# SUP_1_2_1_8.net
KiCad netlist of a schematic drawn in Altium Designer
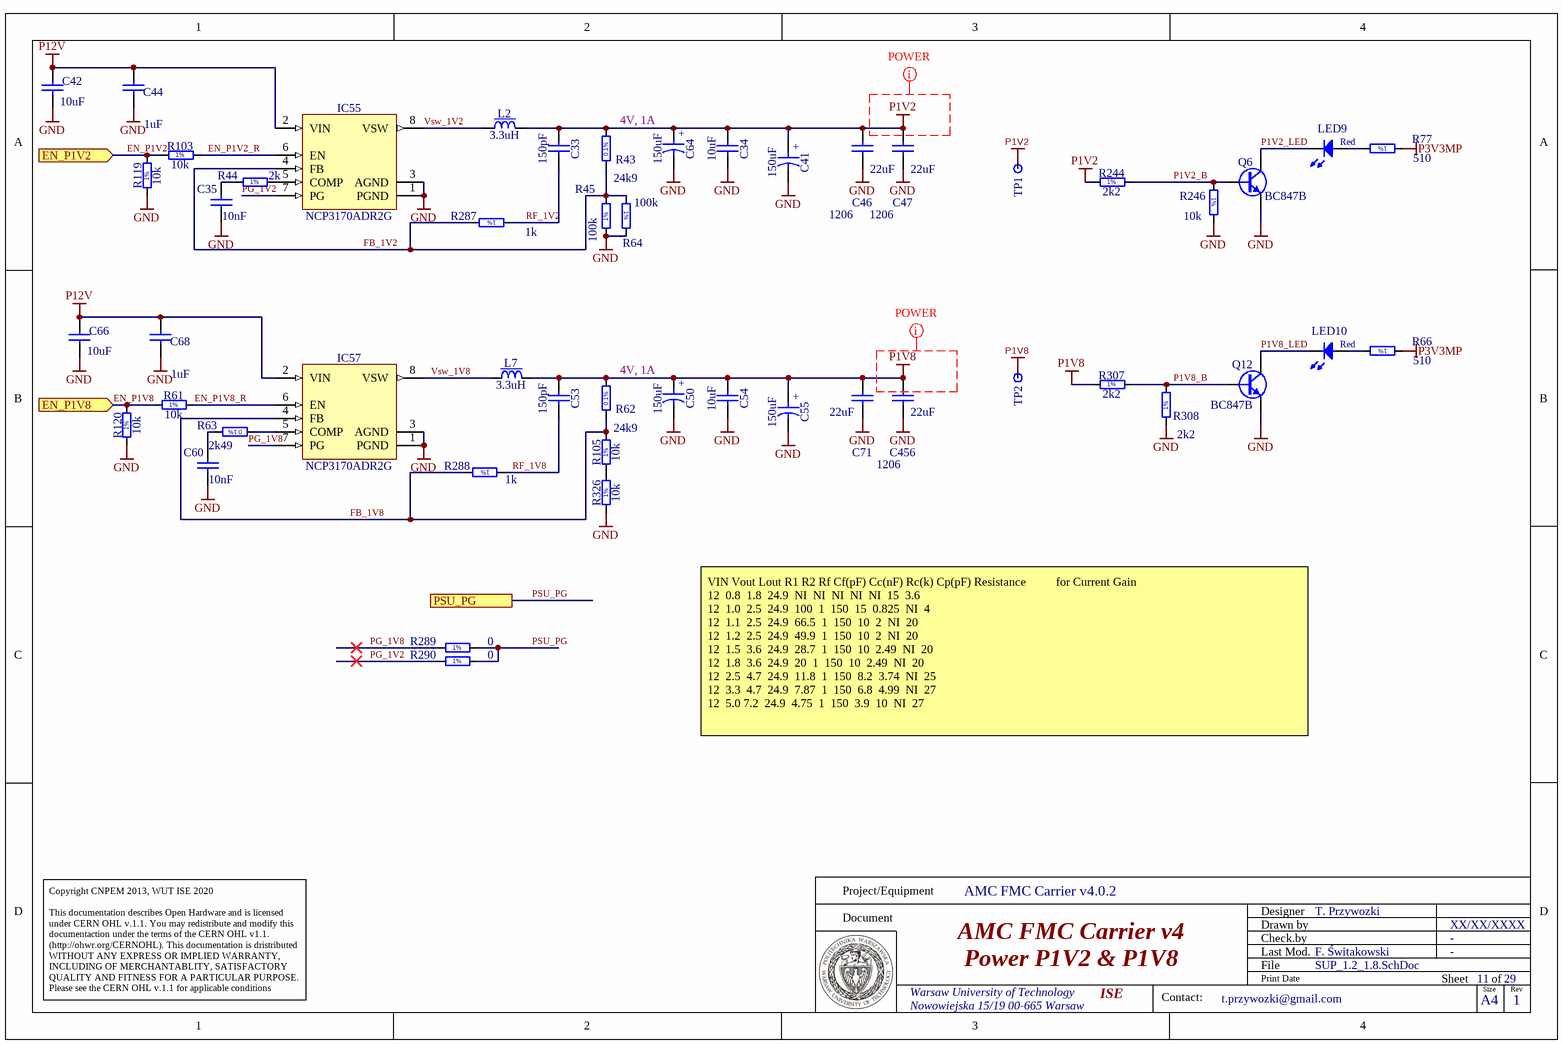
[diagram p0: SUP_1.2_1.8.SchDoc]

(export (version "E")
  (design (tool "Eeschema 10.0.6"))
  (components
    (comp (ref "C33")
      (value "150pF")
      (footprint "CAPC1608X87N")
      (description "Non-polarised capacitor")
      (fields
        (field (name "PART NUMBER") "CC0603_150PF_50V_5%_NP0")
        (field (name "VOLTAGE") "50V")
        (field (name "AUTHOR") "CERN DEM JLC")
      )
      (libsource (lib "Capacitors") (part "Capacitor - non polarized"))
    )
    (comp (ref "C34")
      (value "10uF")
      (footprint "CAPC2012X135N")
      (description "Non-polarised capacitor")
      (fields
        (field (name "PART NUMBER") "CC0805_10UF_16V_10%_X5R")
        (field (name "VOLTAGE") "16V")
        (field (name "AUTHOR") "CERN DEM JLC")
      )
      (libsource (lib "Capacitors") (part "Capacitor - non polarized"))
    )
    (comp (ref "C35")
      (value "10nF")
      (footprint "CAPC1005X55N")
      (description "Non-polarised capacitor")
      (fields
        (field (name "PART NUMBER") "CC0402_10NF_16V_10%_X7R")
        (field (name "VOLTAGE") "16V")
        (field (name "AUTHOR") "CERN DEM JLC")
      )
      (libsource (lib "Capacitors") (part "Capacitor - non polarized"))
    )
    (comp (ref "C41")
      (value "150uF")
      (footprint "CAPMP7343X200N")
      (description "Polarised capacitor")
      (fields
        (field (name "PART NUMBER") "CAEM7343-20_150UF_4V_20%_LESR0016")
        (field (name "VOLTAGE") "4V")
        (field (name "AUTHOR") "CERN DEM JLC")
      )
      (libsource (lib "Capacitors") (part "Capacitor - polarized"))
    )
    (comp (ref "C42")
      (value "10uF")
      (footprint "CAPC2012X135N")
      (description "Non-polarised capacitor")
      (fields
        (field (name "PART NUMBER") "CC0805_10UF_16V_10%_X5R")
        (field (name "VOLTAGE") "16V")
        (field (name "AUTHOR") "CERN DEM JLC")
      )
      (libsource (lib "Capacitors") (part "Capacitor - non polarized"))
    )
    (comp (ref "C44")
      (value "1uF")
      (footprint "CAPC1608X87N")
      (description "Non-polarised capacitor")
      (fields
        (field (name "PART NUMBER") "CC0603_1UF_16V_10%_X7R")
        (field (name "VOLTAGE") "16V")
        (field (name "AUTHOR") "CERN DEM JLC")
      )
      (libsource (lib "Capacitors") (part "Capacitor - non polarized"))
    )
    (comp (ref "C46")
      (value "22uF")
      (footprint "CAPC3216X180N")
      (description "Non-polarised capacitor")
      (fields
        (field (name "PART NUMBER") "CC1206_22UF_10V_10%_X7R")
        (field (name "VOLTAGE") "10V")
        (field (name "CASE") "1206")
        (field (name "AUTHOR") "CERN DEM JLC")
      )
      (libsource (lib "Capacitors") (part "Capacitor - non polarized"))
    )
    (comp (ref "C47")
      (value "22uF")
      (footprint "CAPC3216X180N")
      (description "Non-polarised capacitor")
      (fields
        (field (name "PART NUMBER") "CC1206_22UF_10V_10%_X7R")
        (field (name "VOLTAGE") "10V")
        (field (name "CASE") "1206")
        (field (name "AUTHOR") "CERN DEM JLC")
      )
      (libsource (lib "Capacitors") (part "Capacitor - non polarized"))
    )
    (comp (ref "C50")
      (value "150uF")
      (footprint "CAPMP7343X200N")
      (description "Polarised capacitor")
      (fields
        (field (name "PART NUMBER") "CAEM7343-20_150UF_4V_20%_LESR0016")
        (field (name "VOLTAGE") "4V")
        (field (name "AUTHOR") "CERN DEM JLC")
      )
      (libsource (lib "Capacitors") (part "Capacitor - polarized"))
    )
    (comp (ref "C53")
      (value "150pF")
      (footprint "CAPC1608X87N")
      (description "Non-polarised capacitor")
      (fields
        (field (name "PART NUMBER") "CC0603_150PF_50V_5%_NP0")
        (field (name "VOLTAGE") "50V")
        (field (name "AUTHOR") "CERN DEM JLC")
      )
      (libsource (lib "Capacitors") (part "Capacitor - non polarized"))
    )
    (comp (ref "C54")
      (value "10uF")
      (footprint "CAPC2012X135N")
      (description "Non-polarised capacitor")
      (fields
        (field (name "PART NUMBER") "CC0805_10UF_16V_10%_X5R")
        (field (name "VOLTAGE") "16V")
        (field (name "AUTHOR") "CERN DEM JLC")
      )
      (libsource (lib "Capacitors") (part "Capacitor - non polarized"))
    )
    (comp (ref "C55")
      (value "150uF")
      (footprint "CAPMP7343X200N")
      (description "Polarised capacitor")
      (fields
        (field (name "PART NUMBER") "CAEM7343-20_150UF_4V_20%_LESR0016")
        (field (name "VOLTAGE") "4V")
        (field (name "AUTHOR") "CERN DEM JLC")
      )
      (libsource (lib "Capacitors") (part "Capacitor - polarized"))
    )
    (comp (ref "C60")
      (value "10nF")
      (footprint "CAPC1005X55N")
      (description "Non-polarised capacitor")
      (fields
        (field (name "PART NUMBER") "CC0402_10NF_16V_10%_X7R")
        (field (name "VOLTAGE") "16V")
        (field (name "AUTHOR") "CERN DEM JLC")
      )
      (libsource (lib "Capacitors") (part "Capacitor - non polarized"))
    )
    (comp (ref "C64")
      (value "150uF")
      (footprint "CAPMP7343X200N")
      (description "Polarised capacitor")
      (fields
        (field (name "PART NUMBER") "CAEM7343-20_150UF_4V_20%_LESR0016")
        (field (name "VOLTAGE") "4V")
        (field (name "AUTHOR") "CERN DEM JLC")
      )
      (libsource (lib "Capacitors") (part "Capacitor - polarized"))
    )
    (comp (ref "C66")
      (value "10uF")
      (footprint "CAPC2012X135N")
      (description "Non-polarised capacitor")
      (fields
        (field (name "PART NUMBER") "CC0805_10UF_16V_10%_X5R")
        (field (name "VOLTAGE") "16V")
        (field (name "AUTHOR") "CERN DEM JLC")
      )
      (libsource (lib "Capacitors") (part "Capacitor - non polarized"))
    )
    (comp (ref "C68")
      (value "1uF")
      (footprint "CAPC1608X87N")
      (description "Non-polarised capacitor")
      (fields
        (field (name "PART NUMBER") "CC0603_1UF_16V_10%_X7R")
        (field (name "VOLTAGE") "16V")
        (field (name "AUTHOR") "CERN DEM JLC")
      )
      (libsource (lib "Capacitors") (part "Capacitor - non polarized"))
    )
    (comp (ref "C71")
      (value "22uF")
      (footprint "CAPC3216X180N")
      (description "Non-polarised capacitor")
      (fields
        (field (name "PART NUMBER") "CC1206_22UF_10V_10%_X7R")
        (field (name "VOLTAGE") "10V")
        (field (name "AUTHOR") "CERN DEM JLC")
      )
      (libsource (lib "Capacitors") (part "Capacitor - non polarized"))
    )
    (comp (ref "C456")
      (value "22uF")
      (footprint "CAPC3216X180N")
      (description "Non-polarised capacitor")
      (fields
        (field (name "PART NUMBER") "CC1206_22UF_10V_10%_X7R")
        (field (name "VOLTAGE") "10V")
        (field (name "CASE") "1206")
        (field (name "AUTHOR") "CERN DEM JLC")
      )
      (libsource (lib "Capacitors") (part "Capacitor - non polarized"))
    )
    (comp (ref "IC55")
      (value "NCP3170ADR2G")
      (footprint "SOIC127P600X175-8N")
      (description "Synchronous PWM Switching Converter")
      (fields (field (name "MANUFACTURER") "ON SEMICONDUCTOR") (field (name "AUTHOR") "CERN DEM MR"))
      (libsource (lib "ICs And Semiconductors") (part "NCP3170ADR2G"))
    )
    (comp (ref "IC57")
      (value "NCP3170ADR2G")
      (footprint "SOIC127P600X175-8N")
      (description "Synchronous PWM Switching Converter")
      (fields (field (name "MANUFACTURER") "ON SEMICONDUCTOR") (field (name "AUTHOR") "CERN DEM MR"))
      (libsource (lib "ICs And Semiconductors") (part "NCP3170ADR2G"))
    )
    (comp (ref "L2")
      (value "3.3uH")
      (footprint "IND_WURTH_WE-PD4_L")
      (description "Inductor With Core")
      (fields
        (field (name "PART NUMBER") "IND_3.3UH_20%_WURTH_WE-PD4_74456033")
        (field (name "POWER") "5.3A")
        (field (name "AUTHOR") "CERN DEM JLC")
      )
      (libsource (lib "Inductors & Transformers") (part "Inductor With Magnetic core"))
    )
    (comp (ref "L7")
      (value "3.3uH")
      (footprint "IND_WURTH_WE-PD4_L")
      (description "Inductor With Core")
      (fields
        (field (name "PART NUMBER") "IND_3.3UH_20%_WURTH_WE-PD4_74456033")
        (field (name "POWER") "5.3A")
        (field (name "AUTHOR") "CERN DEM JLC")
      )
      (libsource (lib "Inductors & Transformers") (part "Inductor With Magnetic core"))
    )
    (comp (ref "LED9")
      (value "Red")
      (footprint "LED_KINGBRIGHT_KPH-1608SURCK")
      (description "LED Red 1C 2A")
      (fields
        (field (name "PART NUMBER") "LED_KINGBRIGHT_KPH-1608SURCK")
        (field (name "MANUFACTURER") "KINGBRIGHT")
        (field (name "AUTHOR") "CERN DEM JLC")
      )
      (libsource (lib "ICs And Semiconductors") (part "LED Red 1C 2A"))
    )
    (comp (ref "LED10")
      (value "Red")
      (footprint "LED_KINGBRIGHT_KPH-1608SURCK")
      (description "LED Red 1C 2A")
      (fields
        (field (name "PART NUMBER") "LED_KINGBRIGHT_KPH-1608SURCK")
        (field (name "MANUFACTURER") "KINGBRIGHT")
        (field (name "AUTHOR") "CERN DEM JLC")
      )
      (libsource (lib "ICs And Semiconductors") (part "LED Red 1C 2A"))
    )
    (comp (ref "Q6")
      (value "BC847B")
      (footprint "SOT95P230X110-3N")
      (description "NPN Transistor")
      (fields (field (name "MANUFACTURER") "NXP SEMICONDUCTORS") (field (name "AUTHOR") "CERN DEM JLC"))
      (libsource (lib "ICs And Semiconductors") (part "NPN B1 E2 C3"))
    )
    (comp (ref "Q12")
      (value "BC847B")
      (footprint "SOT95P230X110-3N")
      (description "NPN Transistor")
      (fields (field (name "MANUFACTURER") "NXP SEMICONDUCTORS") (field (name "AUTHOR") "CERN DEM JLC"))
      (libsource (lib "ICs And Semiconductors") (part "NPN B1 E2 C3"))
    )
    (comp (ref "R43")
      (value "24k9")
      (footprint "RESC1608X55N")
      (description "Resistor - 0.1%")
      (fields
        (field (name "PART NUMBER") "R0603_24K9_0.1%_0.063W_10PPM")
        (field (name "POWER") "0.063W")
        (field (name "AUTHOR") "CERN DEM JLC")
      )
      (libsource (lib "Resistors") (part "Resistor - 0.1%"))
    )
    (comp (ref "R44")
      (value "2k")
      (footprint "RESC1608X55N")
      (description "Resistor - 1%")
      (fields
        (field (name "PART NUMBER") "R0603_2K_1%_0.1W_100PPM")
        (field (name "POWER") "0.1W")
        (field (name "AUTHOR") "CERN DEM JLC")
      )
      (libsource (lib "Resistors") (part "Resistor - 1%"))
    )
    (comp (ref "R45")
      (value "100k")
      (footprint "RESC1005X40N")
      (description "Resistor - 1%")
      (fields
        (field (name "PART NUMBER") "R0402_100K_1%_0.0625W_100PPM")
        (field (name "POWER") "0.0625W")
        (field (name "AUTHOR") "CERN DEM JLC")
      )
      (libsource (lib "Resistors") (part "Resistor - 1%"))
    )
    (comp (ref "R61")
      (value "10k")
      (footprint "RESC1005X40N")
      (description "Resistor - 1%")
      (fields
        (field (name "PART NUMBER") "R0402_10K_1%_0.0625W_100PPM")
        (field (name "POWER") "0.0625W")
        (field (name "AUTHOR") "CERN DEM JLC")
      )
      (libsource (lib "Resistors") (part "Resistor - 1%"))
    )
    (comp (ref "R62")
      (value "24k9")
      (footprint "RESC1608X55N")
      (description "Resistor - 0.1%")
      (fields
        (field (name "PART NUMBER") "R0603_24K9_0.1%_0.063W_10PPM")
        (field (name "POWER") "0.063W")
        (field (name "AUTHOR") "CERN DEM JLC")
      )
      (libsource (lib "Resistors") (part "Resistor - 0.1%"))
    )
    (comp (ref "R63")
      (value "2k49")
      (footprint "RESC1608X55N")
      (description "Resistor - 0.1%")
      (fields
        (field (name "PART NUMBER") "R0603_2K49_0.1%_0.063W_10PPM")
        (field (name "POWER") "0.063W")
        (field (name "AUTHOR") "CERN DEM JLC")
      )
      (libsource (lib "Resistors") (part "Resistor - 0.1%"))
    )
    (comp (ref "R64")
      (value "100k")
      (footprint "RESC1005X40N")
      (description "Resistor - 1%")
      (fields
        (field (name "PART NUMBER") "R0402_100K_1%_0.0625W_100PPM")
        (field (name "POWER") "0.0625W")
        (field (name "AUTHOR") "CERN DEM JLC")
      )
      (libsource (lib "Resistors") (part "Resistor - 1%"))
    )
    (comp (ref "R66")
      (value "510")
      (footprint "RESC1005X40N")
      (description "Resistor - 1%")
      (fields
        (field (name "PART NUMBER") "R0402_510R_1%_0.0625W_100PPM")
        (field (name "POWER") "0.0625W")
        (field (name "AUTHOR") "CERN DEM JLC")
      )
      (libsource (lib "Resistors") (part "Resistor - 1%"))
    )
    (comp (ref "R77")
      (value "510")
      (footprint "RESC1005X40N")
      (description "Resistor - 1%")
      (fields
        (field (name "PART NUMBER") "R0402_510R_1%_0.0625W_100PPM")
        (field (name "POWER") "0.0625W")
        (field (name "AUTHOR") "CERN DEM JLC")
      )
      (libsource (lib "Resistors") (part "Resistor - 1%"))
    )
    (comp (ref "R103")
      (value "10k")
      (footprint "RESC1005X40N")
      (description "Resistor - 1%")
      (fields
        (field (name "PART NUMBER") "R0402_10K_1%_0.0625W_100PPM")
        (field (name "POWER") "0.0625W")
        (field (name "AUTHOR") "CERN DEM JLC")
      )
      (libsource (lib "Resistors") (part "Resistor - 1%"))
    )
    (comp (ref "R105")
      (value "10k")
      (footprint "RESC1005X40N")
      (description "Resistor - 1%")
      (fields
        (field (name "PART NUMBER") "R0402_10K_1%_0.0625W_100PPM")
        (field (name "POWER") "0.0625W")
        (field (name "AUTHOR") "CERN DEM JLC")
      )
      (libsource (lib "Resistors") (part "Resistor - 1%"))
    )
    (comp (ref "R119")
      (value "10k")
      (footprint "RESC1005X40N")
      (description "Resistor - 1%")
      (fields
        (field (name "PART NUMBER") "R0402_10K_1%_0.0625W_100PPM")
        (field (name "POWER") "0.0625W")
        (field (name "AUTHOR") "CERN DEM JLC")
      )
      (libsource (lib "Resistors") (part "Resistor - 1%"))
    )
    (comp (ref "R120")
      (value "10k")
      (footprint "RESC1005X40N")
      (description "Resistor - 1%")
      (fields
        (field (name "PART NUMBER") "R0402_10K_1%_0.0625W_100PPM")
        (field (name "POWER") "0.0625W")
        (field (name "AUTHOR") "CERN DEM JLC")
      )
      (libsource (lib "Resistors") (part "Resistor - 1%"))
    )
    (comp (ref "R244")
      (value "2k2")
      (footprint "RESC1005X40N")
      (description "Resistor - 1%")
      (fields
        (field (name "PART NUMBER") "R0402_2K2_1%_0.0625W_100PPM")
        (field (name "POWER") "0.0625W")
        (field (name "AUTHOR") "CERN DEM JLC")
      )
      (libsource (lib "Resistors") (part "Resistor - 1%"))
    )
    (comp (ref "R246")
      (value "10k")
      (footprint "RESC1005X40N")
      (description "Resistor - 1%")
      (fields
        (field (name "PART NUMBER") "R0402_10K_1%_0.0625W_100PPM")
        (field (name "POWER") "0.0625W")
        (field (name "AUTHOR") "CERN DEM JLC")
      )
      (libsource (lib "Resistors") (part "Resistor - 1%"))
    )
    (comp (ref "R287")
      (value "1k")
      (footprint "RESC1005X40N")
      (description "Resistor - 1%")
      (fields
        (field (name "PART NUMBER") "R0402_1K_1%_0.0625W_100PPM")
        (field (name "POWER") "0.0625W")
        (field (name "AUTHOR") "CERN DEM JLC")
      )
      (libsource (lib "Resistors") (part "Resistor - 1%"))
    )
    (comp (ref "R288")
      (value "1k")
      (footprint "RESC1005X40N")
      (description "Resistor - 1%")
      (fields
        (field (name "PART NUMBER") "R0402_1K_1%_0.0625W_100PPM")
        (field (name "POWER") "0.0625W")
        (field (name "AUTHOR") "CERN DEM JLC")
      )
      (libsource (lib "Resistors") (part "Resistor - 1%"))
    )
    (comp (ref "R289")
      (value "0")
      (footprint "RESC1005X40N")
      (description "Resistor - 1%")
      (fields
        (field (name "PART NUMBER") "R0402_0R_JUMPER")
        (field (name "MANUFACTURER") "GENERIC")
        (field (name "AUTHOR") "CERN DEM JLC")
      )
      (libsource (lib "Resistors") (part "Resistor - 1%"))
    )
    (comp (ref "R290")
      (value "0")
      (footprint "RESC1005X40N")
      (description "Resistor - 1%")
      (fields
        (field (name "PART NUMBER") "R0402_0R_JUMPER")
        (field (name "MANUFACTURER") "GENERIC")
        (field (name "AUTHOR") "CERN DEM JLC")
      )
      (libsource (lib "Resistors") (part "Resistor - 1%"))
    )
    (comp (ref "R307")
      (value "2k2")
      (footprint "RESC1005X40N")
      (description "Resistor - 1%")
      (fields
        (field (name "PART NUMBER") "R0402_2K2_1%_0.0625W_100PPM")
        (field (name "POWER") "0.0625W")
        (field (name "AUTHOR") "CERN DEM JLC")
      )
      (libsource (lib "Resistors") (part "Resistor - 1%"))
    )
    (comp (ref "R308")
      (value "2k2")
      (footprint "RESC1005X40N")
      (description "Resistor - 1%")
      (fields
        (field (name "PART NUMBER") "R0402_2K2_1%_0.0625W_100PPM")
        (field (name "POWER") "0.0625W")
        (field (name "AUTHOR") "CERN DEM JLC")
      )
      (libsource (lib "Resistors") (part "Resistor - 1%"))
    )
    (comp (ref "R326")
      (value "10k")
      (footprint "RESC1005X40N")
      (description "Resistor - 1%")
      (fields
        (field (name "PART NUMBER") "R0402_10K_1%_0.0625W_100PPM")
        (field (name "POWER") "0.0625W")
        (field (name "AUTHOR") "CERN DEM JLC")
      )
      (libsource (lib "Resistors") (part "Resistor - 1%"))
    )
    (comp (ref "TP1")
      (value "Test Point")
      (footprint "TPS127")
      (fields (field (name "PART NUMBER") "SMD_PAD_1.27X1.27MM") (field (name "AUTHOR") "CERN DEM JLC"))
      (libsource (lib "Eletro-mechanical") (part "Test Point"))
    )
    (comp (ref "TP2")
      (value "Test Point")
      (footprint "TPS127")
      (fields (field (name "PART NUMBER") "SMD_PAD_1.27X1.27MM") (field (name "AUTHOR") "CERN DEM JLC"))
      (libsource (lib "Eletro-mechanical") (part "Test Point"))
    )
  )
  (nets
    (net (code "1") (name "/EN_P1V2") (class "Default")
      (node (ref "R103") (pin "1") (pinfunction "1_1") (pintype "passive"))
      (node (ref "R119") (pin "2") (pinfunction "2_2") (pintype "passive"))
    )
    (net (code "2") (name "/EN_P1V2_R") (class "Default")
      (node (ref "IC55") (pin "6") (pinfunction "EN_6") (pintype "input"))
      (node (ref "R103") (pin "2") (pinfunction "2_2") (pintype "passive"))
    )
    (net (code "3") (name "/EN_P1V8") (class "Default")
      (node (ref "R120") (pin "2") (pinfunction "2_2") (pintype "passive"))
      (node (ref "R61") (pin "1") (pinfunction "1_1") (pintype "passive"))
    )
    (net (code "4") (name "/EN_P1V8_R") (class "Default")
      (node (ref "IC57") (pin "6") (pinfunction "EN_6") (pintype "input"))
      (node (ref "R61") (pin "2") (pinfunction "2_2") (pintype "passive"))
    )
    (net (code "5") (name "/FB_1V2") (class "Default")
      (node (ref "IC55") (pin "4") (pinfunction "FB_4") (pintype "input"))
      (node (ref "R287") (pin "2") (pinfunction "2_2") (pintype "passive"))
      (node (ref "R43") (pin "1") (pinfunction "1_1") (pintype "passive"))
      (node (ref "R45") (pin "2") (pinfunction "2_2") (pintype "passive"))
      (node (ref "R64") (pin "1") (pinfunction "1_1") (pintype "passive"))
    )
    (net (code "6") (name "/FB_1V8") (class "Default")
      (node (ref "IC57") (pin "4") (pinfunction "FB_4") (pintype "input"))
      (node (ref "R105") (pin "2") (pinfunction "2_2") (pintype "passive"))
      (node (ref "R288") (pin "2") (pinfunction "2_2") (pintype "passive"))
      (node (ref "R62") (pin "1") (pinfunction "1_1") (pintype "passive"))
    )
    (net (code "7") (name "/P1V2_B") (class "Default")
      (node (ref "Q6") (pin "1") (pinfunction "B_1") (pintype "passive"))
      (node (ref "R244") (pin "2") (pinfunction "2_2") (pintype "passive"))
      (node (ref "R246") (pin "1") (pinfunction "1_1") (pintype "passive"))
    )
    (net (code "8") (name "/P1V2_LED") (class "Default")
      (node (ref "LED9") (pin "1") (pinfunction "C_1") (pintype "passive"))
      (node (ref "Q6") (pin "3") (pinfunction "C_3") (pintype "passive"))
    )
    (net (code "9") (name "/P1V8_B") (class "Default")
      (node (ref "Q12") (pin "1") (pinfunction "B_1") (pintype "passive"))
      (node (ref "R307") (pin "2") (pinfunction "2_2") (pintype "passive"))
      (node (ref "R308") (pin "2") (pinfunction "2_2") (pintype "passive"))
    )
    (net (code "10") (name "/P1V8_LED") (class "Default")
      (node (ref "LED10") (pin "1") (pinfunction "C_1") (pintype "passive"))
      (node (ref "Q12") (pin "3") (pinfunction "C_3") (pintype "passive"))
    )
    (net (code "11") (name "/PG_1V2") (class "Default")
      (node (ref "IC55") (pin "7") (pinfunction "PG_7") (pintype "input"))
      (node (ref "R290") (pin "2") (pinfunction "2_2") (pintype "passive"))
    )
    (net (code "12") (name "/PG_1V8") (class "Default")
      (node (ref "IC57") (pin "7") (pinfunction "PG_7") (pintype "input"))
      (node (ref "R289") (pin "2") (pinfunction "2_2") (pintype "passive"))
    )
    (net (code "13") (name "/PSU_PG") (class "Default")
      (node (ref "R289") (pin "1") (pinfunction "1_1") (pintype "passive"))
      (node (ref "R290") (pin "1") (pinfunction "1_1") (pintype "passive"))
    )
    (net (code "14") (name "/RF_1V2") (class "Default")
      (node (ref "C33") (pin "2") (pinfunction "2_2") (pintype "passive"))
      (node (ref "R287") (pin "1") (pinfunction "1_1") (pintype "passive"))
    )
    (net (code "15") (name "/RF_1V8") (class "Default")
      (node (ref "C53") (pin "2") (pinfunction "2_2") (pintype "passive"))
      (node (ref "R288") (pin "1") (pinfunction "1_1") (pintype "passive"))
    )
    (net (code "16") (name "/Vsw_1V2") (class "Default")
      (node (ref "IC55") (pin "8") (pinfunction "VSW_8") (pintype "output"))
      (node (ref "L2") (pin "1") (pinfunction "1_1") (pintype "passive"))
    )
    (net (code "17") (name "/Vsw_1V8") (class "Default")
      (node (ref "IC57") (pin "8") (pinfunction "VSW_8") (pintype "output"))
      (node (ref "L7") (pin "1") (pinfunction "1_1") (pintype "passive"))
    )
    (net (code "18") (name "GND") (class "Default")
      (node (ref "C34") (pin "2") (pinfunction "2_2") (pintype "passive"))
      (node (ref "C35") (pin "2") (pinfunction "2_2") (pintype "passive"))
      (node (ref "C41") (pin "2") (pinfunction "2_2") (pintype "passive"))
      (node (ref "C42") (pin "1") (pinfunction "1_1") (pintype "passive"))
      (node (ref "C44") (pin "1") (pinfunction "1_1") (pintype "passive"))
      (node (ref "C456") (pin "2") (pinfunction "2_2") (pintype "passive"))
      (node (ref "C46") (pin "2") (pinfunction "2_2") (pintype "passive"))
      (node (ref "C47") (pin "2") (pinfunction "2_2") (pintype "passive"))
      (node (ref "C50") (pin "2") (pinfunction "2_2") (pintype "passive"))
      (node (ref "C54") (pin "2") (pinfunction "2_2") (pintype "passive"))
      (node (ref "C55") (pin "2") (pinfunction "2_2") (pintype "passive"))
      (node (ref "C60") (pin "1") (pinfunction "1_1") (pintype "passive"))
      (node (ref "C64") (pin "2") (pinfunction "2_2") (pintype "passive"))
      (node (ref "C66") (pin "1") (pinfunction "1_1") (pintype "passive"))
      (node (ref "C68") (pin "1") (pinfunction "1_1") (pintype "passive"))
      (node (ref "C71") (pin "2") (pinfunction "2_2") (pintype "passive"))
      (node (ref "IC55") (pin "1") (pinfunction "PGND_1") (pintype "power_in"))
      (node (ref "IC55") (pin "3") (pinfunction "AGND_3") (pintype "power_in"))
      (node (ref "IC57") (pin "1") (pinfunction "PGND_1") (pintype "power_in"))
      (node (ref "IC57") (pin "3") (pinfunction "AGND_3") (pintype "power_in"))
      (node (ref "Q12") (pin "2") (pinfunction "E_2") (pintype "passive"))
      (node (ref "Q6") (pin "2") (pinfunction "E_2") (pintype "passive"))
      (node (ref "R119") (pin "1") (pinfunction "1_1") (pintype "passive"))
      (node (ref "R120") (pin "1") (pinfunction "1_1") (pintype "passive"))
      (node (ref "R246") (pin "2") (pinfunction "2_2") (pintype "passive"))
      (node (ref "R308") (pin "1") (pinfunction "1_1") (pintype "passive"))
      (node (ref "R326") (pin "1") (pinfunction "1_1") (pintype "passive"))
      (node (ref "R45") (pin "1") (pinfunction "1_1") (pintype "passive"))
      (node (ref "R64") (pin "2") (pinfunction "2_2") (pintype "passive"))
    )
    (net (code "19") (name "Net-(C35-Pad1)") (class "Default")
      (node (ref "C35") (pin "1") (pinfunction "1_1") (pintype "passive"))
      (node (ref "R44") (pin "2") (pinfunction "2_2") (pintype "passive"))
    )
    (net (code "20") (name "Net-(C60-Pad2)") (class "Default")
      (node (ref "C60") (pin "2") (pinfunction "2_2") (pintype "passive"))
      (node (ref "R63") (pin "1") (pinfunction "1_1") (pintype "passive"))
    )
    (net (code "21") (name "Net-(IC55-COMP)") (class "Default")
      (node (ref "IC55") (pin "5") (pinfunction "COMP_5") (pintype "input"))
      (node (ref "R44") (pin "1") (pinfunction "1_1") (pintype "passive"))
    )
    (net (code "22") (name "Net-(IC57-COMP)") (class "Default")
      (node (ref "IC57") (pin "5") (pinfunction "COMP_5") (pintype "input"))
      (node (ref "R63") (pin "2") (pinfunction "2_2") (pintype "passive"))
    )
    (net (code "23") (name "Net-(LED9-A)") (class "Default")
      (node (ref "LED9") (pin "2") (pinfunction "A_2") (pintype "passive"))
      (node (ref "R77") (pin "2") (pinfunction "2_2") (pintype "passive"))
    )
    (net (code "24") (name "Net-(LED10-A)") (class "Default")
      (node (ref "LED10") (pin "2") (pinfunction "A_2") (pintype "passive"))
      (node (ref "R66") (pin "2") (pinfunction "2_2") (pintype "passive"))
    )
    (net (code "25") (name "Net-(R105-Pad1)") (class "Default")
      (node (ref "R105") (pin "1") (pinfunction "1_1") (pintype "passive"))
      (node (ref "R326") (pin "2") (pinfunction "2_2") (pintype "passive"))
    )
    (net (code "26") (name "P1V2") (class "Default")
      (node (ref "C33") (pin "1") (pinfunction "1_1") (pintype "passive"))
      (node (ref "C34") (pin "1") (pinfunction "1_1") (pintype "passive"))
      (node (ref "C41") (pin "1") (pinfunction "1_1") (pintype "passive"))
      (node (ref "C46") (pin "1") (pinfunction "1_1") (pintype "passive"))
      (node (ref "C47") (pin "1") (pinfunction "1_1") (pintype "passive"))
      (node (ref "C64") (pin "1") (pinfunction "1_1") (pintype "passive"))
      (node (ref "L2") (pin "2") (pinfunction "2_2") (pintype "passive"))
      (node (ref "R244") (pin "1") (pinfunction "1_1") (pintype "passive"))
      (node (ref "R43") (pin "2") (pinfunction "2_2") (pintype "passive"))
      (node (ref "TP1") (pin "1") (pinfunction "1_1") (pintype "bidirectional"))
    )
    (net (code "27") (name "P1V8") (class "Default")
      (node (ref "C456") (pin "1") (pinfunction "1_1") (pintype "passive"))
      (node (ref "C50") (pin "1") (pinfunction "1_1") (pintype "passive"))
      (node (ref "C53") (pin "1") (pinfunction "1_1") (pintype "passive"))
      (node (ref "C54") (pin "1") (pinfunction "1_1") (pintype "passive"))
      (node (ref "C55") (pin "1") (pinfunction "1_1") (pintype "passive"))
      (node (ref "C71") (pin "1") (pinfunction "1_1") (pintype "passive"))
      (node (ref "L7") (pin "2") (pinfunction "2_2") (pintype "passive"))
      (node (ref "R307") (pin "1") (pinfunction "1_1") (pintype "passive"))
      (node (ref "R62") (pin "2") (pinfunction "2_2") (pintype "passive"))
      (node (ref "TP2") (pin "1") (pinfunction "1_1") (pintype "bidirectional"))
    )
    (net (code "28") (name "P3V3MP") (class "Default")
      (node (ref "R66") (pin "1") (pinfunction "1_1") (pintype "passive"))
      (node (ref "R77") (pin "1") (pinfunction "1_1") (pintype "passive"))
    )
    (net (code "29") (name "P12V") (class "Default")
      (node (ref "C42") (pin "2") (pinfunction "2_2") (pintype "passive"))
      (node (ref "C44") (pin "2") (pinfunction "2_2") (pintype "passive"))
      (node (ref "C66") (pin "2") (pinfunction "2_2") (pintype "passive"))
      (node (ref "C68") (pin "2") (pinfunction "2_2") (pintype "passive"))
      (node (ref "IC55") (pin "2") (pinfunction "VIN_2") (pintype "input"))
      (node (ref "IC57") (pin "2") (pinfunction "VIN_2") (pintype "input"))
    )
  )
)
